# Schematic.net
KiCad netlist of a schematic drawn in EAGLE
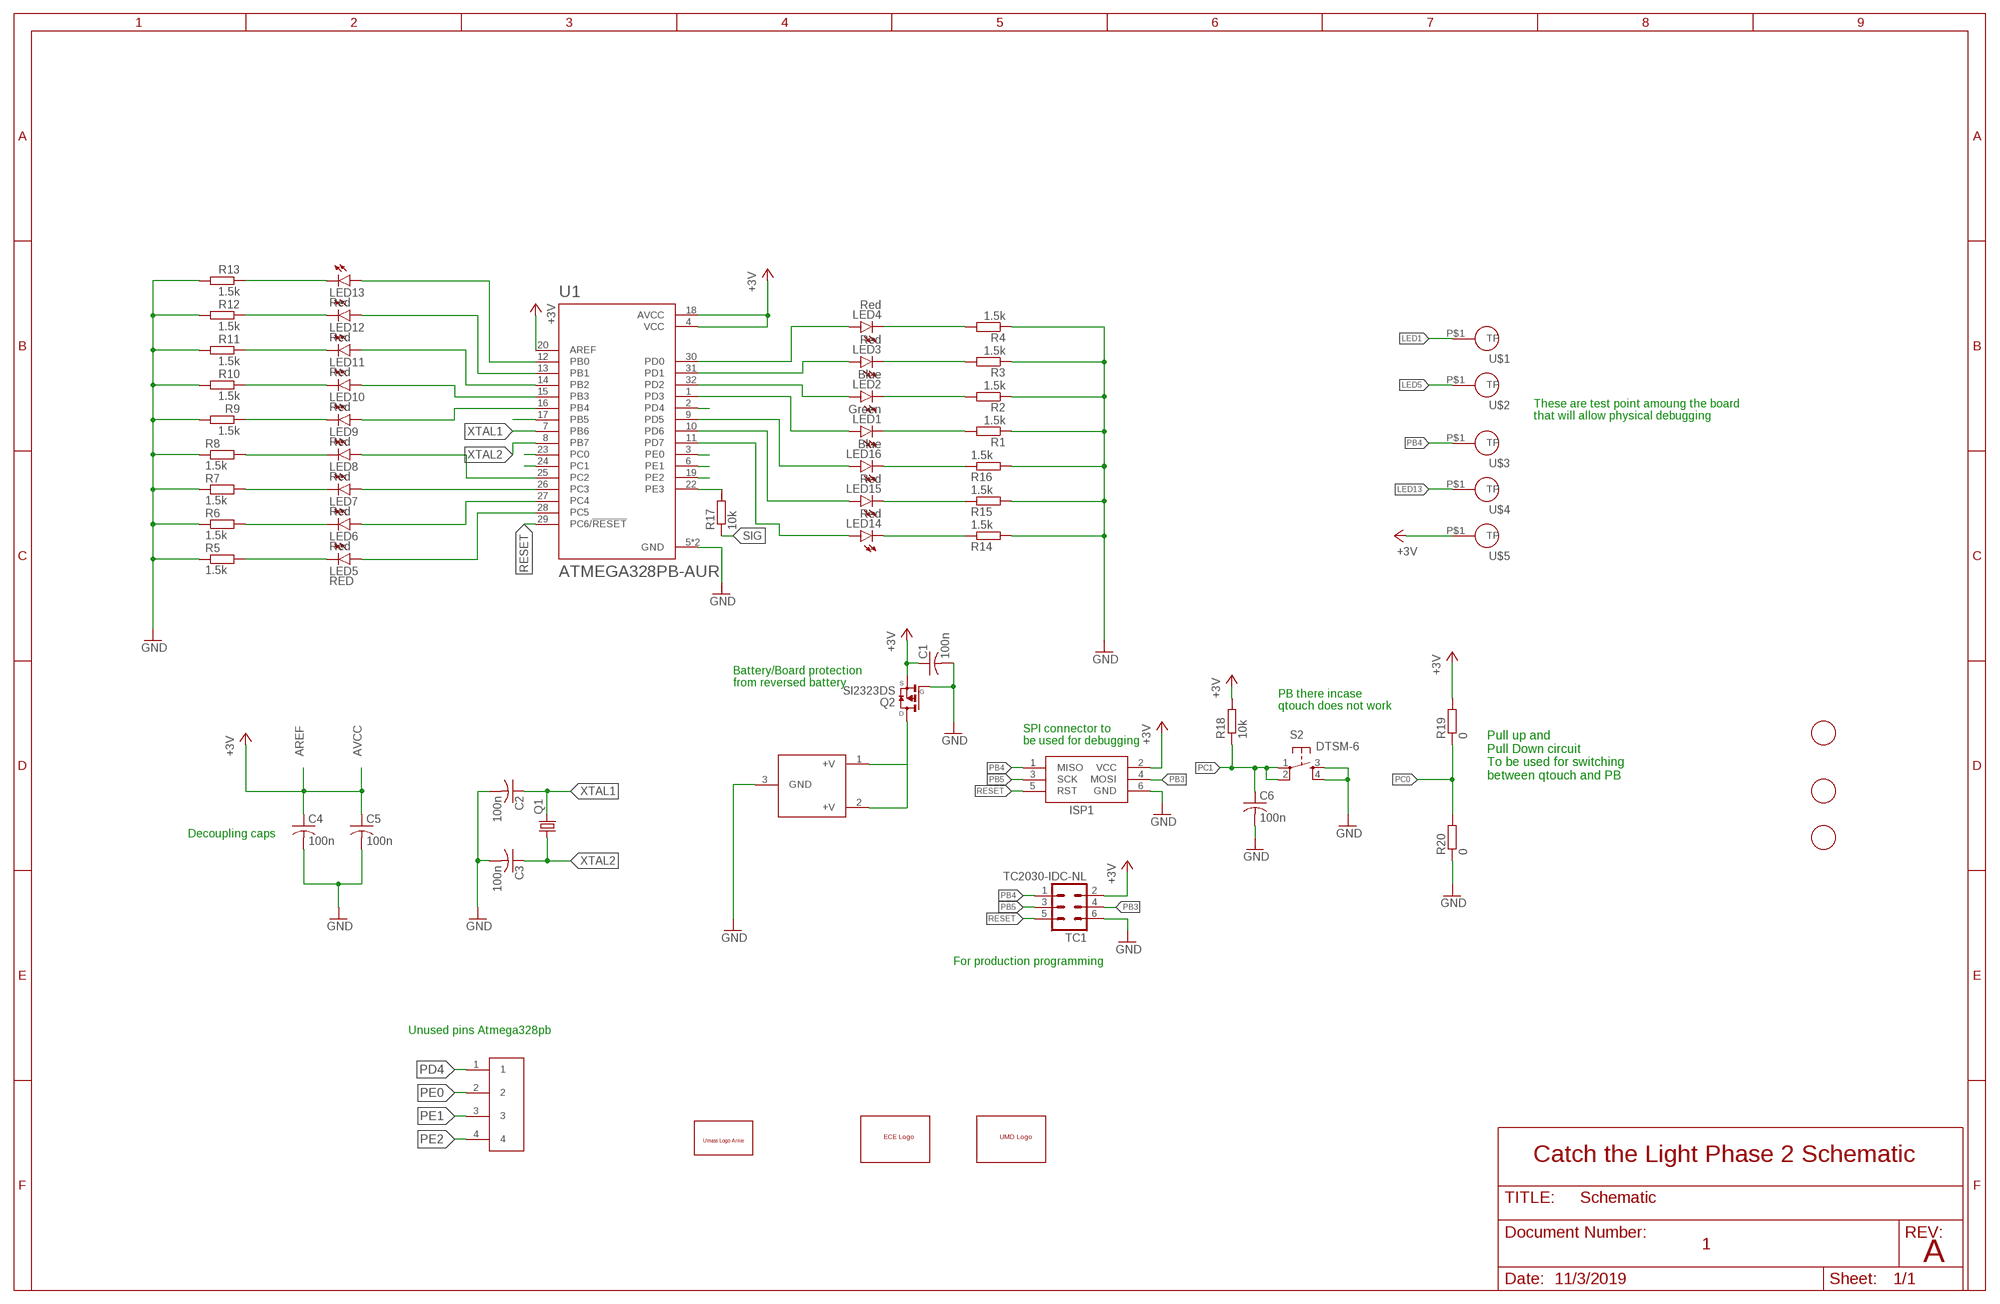
[diagram p0: schematic, sheet 1]

(export (version "E")
  (design (tool "Eeschema 10.0.6"))
  (components
    (comp (ref "C1")
      (value "100n")
      (footprint "eagle-import:C0805")
      (libsource (lib "eagle-import") (part "C-USC0805"))
    )
    (comp (ref "C2")
      (value "100n")
      (footprint "eagle-import:C0805")
      (libsource (lib "eagle-import") (part "C-USC0805"))
    )
    (comp (ref "C3")
      (value "100n")
      (footprint "eagle-import:C0805")
      (libsource (lib "eagle-import") (part "C-USC0805"))
    )
    (comp (ref "C4")
      (value "100n")
      (footprint "eagle-import:C0805")
      (libsource (lib "eagle-import") (part "C-USC0805"))
    )
    (comp (ref "C5")
      (value "100n")
      (footprint "eagle-import:C0805")
      (libsource (lib "eagle-import") (part "C-USC0805"))
    )
    (comp (ref "C6")
      (value "100n")
      (footprint "eagle-import:C0805")
      (libsource (lib "eagle-import") (part "C-USC0805"))
    )
    (comp (ref "CR2032")
      (value "BC-2003SMD")
      (footprint "eagle-import:BC-2003")
      (libsource (lib "eagle-import") (part "BC-2003SMD"))
    )
    (comp (ref "ISP1")
      (value "AVRISP-6")
      (footprint "eagle-import:AVRISP")
      (libsource (lib "eagle-import") (part "AVRISP-6"))
    )
    (comp (ref "LED1")
      (value "Green")
      (footprint "eagle-import:CHIP-LED0805")
      (libsource (lib "eagle-import") (part "LEDCHIP-LED0805"))
    )
    (comp (ref "LED2")
      (value "Blue")
      (footprint "eagle-import:CHIP-LED0805")
      (libsource (lib "eagle-import") (part "LEDCHIP-LED0805"))
    )
    (comp (ref "LED3")
      (value "Red")
      (footprint "eagle-import:CHIP-LED0805")
      (libsource (lib "eagle-import") (part "LEDCHIP-LED0805"))
    )
    (comp (ref "LED4")
      (value "Red")
      (footprint "eagle-import:CHIP-LED0805")
      (libsource (lib "eagle-import") (part "LEDCHIP-LED0805"))
    )
    (comp (ref "LED5")
      (value "RED")
      (footprint "eagle-import:CHIP-LED0805")
      (libsource (lib "eagle-import") (part "LEDCHIP-LED0805"))
    )
    (comp (ref "LED6")
      (value "Red")
      (footprint "eagle-import:CHIP-LED0805")
      (libsource (lib "eagle-import") (part "LEDCHIP-LED0805"))
    )
    (comp (ref "LED7")
      (value "Red")
      (footprint "eagle-import:CHIP-LED0805")
      (libsource (lib "eagle-import") (part "LEDCHIP-LED0805"))
    )
    (comp (ref "LED8")
      (value "Red")
      (footprint "eagle-import:CHIP-LED0805")
      (libsource (lib "eagle-import") (part "LEDCHIP-LED0805"))
    )
    (comp (ref "LED9")
      (value "Red")
      (footprint "eagle-import:CHIP-LED0805")
      (libsource (lib "eagle-import") (part "LEDCHIP-LED0805"))
    )
    (comp (ref "LED10")
      (value "Red")
      (footprint "eagle-import:CHIP-LED0805")
      (libsource (lib "eagle-import") (part "LEDCHIP-LED0805"))
    )
    (comp (ref "LED11")
      (value "Red")
      (footprint "eagle-import:CHIP-LED0805")
      (libsource (lib "eagle-import") (part "LEDCHIP-LED0805"))
    )
    (comp (ref "LED12")
      (value "Red")
      (footprint "eagle-import:CHIP-LED0805")
      (libsource (lib "eagle-import") (part "LEDCHIP-LED0805"))
    )
    (comp (ref "LED13")
      (value "Red")
      (footprint "eagle-import:CHIP-LED0805")
      (libsource (lib "eagle-import") (part "LEDCHIP-LED0805"))
    )
    (comp (ref "LED14")
      (value "Red")
      (footprint "eagle-import:CHIP-LED0805")
      (libsource (lib "eagle-import") (part "LEDCHIP-LED0805"))
    )
    (comp (ref "LED15")
      (value "Red")
      (footprint "eagle-import:CHIP-LED0805")
      (libsource (lib "eagle-import") (part "LEDCHIP-LED0805"))
    )
    (comp (ref "LED16")
      (value "Blue")
      (footprint "eagle-import:CHIP-LED0805")
      (libsource (lib "eagle-import") (part "LEDCHIP-LED0805"))
    )
    (comp (ref "Q1")
      (value "CRYSTALHC49UP")
      (footprint "eagle-import:HC49UP")
      (libsource (lib "eagle-import") (part "CRYSTALHC49UP"))
    )
    (comp (ref "Q2")
      (value "SI2323DS")
      (footprint "eagle-import:SOT23")
      (fields (field (name "MF") "Vishay Siliconix"))
      (libsource (lib "eagle-import") (part "SI2323DS"))
    )
    (comp (ref "R1")
      (value "1.5k")
      (footprint "eagle-import:R0805")
      (libsource (lib "eagle-import") (part "R-EU_R0805"))
    )
    (comp (ref "R2")
      (value "1.5k")
      (footprint "eagle-import:R0805")
      (libsource (lib "eagle-import") (part "R-EU_R0805"))
    )
    (comp (ref "R3")
      (value "1.5k")
      (footprint "eagle-import:R0805")
      (libsource (lib "eagle-import") (part "R-EU_R0805"))
    )
    (comp (ref "R4")
      (value "1.5k")
      (footprint "eagle-import:R0805")
      (libsource (lib "eagle-import") (part "R-EU_R0805"))
    )
    (comp (ref "R5")
      (value "1.5k")
      (footprint "eagle-import:R0805")
      (libsource (lib "eagle-import") (part "R-EU_R0805"))
    )
    (comp (ref "R6")
      (value "1.5k")
      (footprint "eagle-import:R0805")
      (libsource (lib "eagle-import") (part "R-EU_R0805"))
    )
    (comp (ref "R7")
      (value "1.5k")
      (footprint "eagle-import:R0805")
      (libsource (lib "eagle-import") (part "R-EU_R0805"))
    )
    (comp (ref "R8")
      (value "1.5k")
      (footprint "eagle-import:R0805")
      (libsource (lib "eagle-import") (part "R-EU_R0805"))
    )
    (comp (ref "R9")
      (value "1.5k")
      (footprint "eagle-import:R0805")
      (libsource (lib "eagle-import") (part "R-EU_R0805"))
    )
    (comp (ref "R10")
      (value "1.5k")
      (footprint "eagle-import:R0805")
      (libsource (lib "eagle-import") (part "R-EU_R0805"))
    )
    (comp (ref "R11")
      (value "1.5k")
      (footprint "eagle-import:R0805")
      (libsource (lib "eagle-import") (part "R-EU_R0805"))
    )
    (comp (ref "R12")
      (value "1.5k")
      (footprint "eagle-import:R0805")
      (libsource (lib "eagle-import") (part "R-EU_R0805"))
    )
    (comp (ref "R13")
      (value "1.5k")
      (footprint "eagle-import:R0805")
      (libsource (lib "eagle-import") (part "R-EU_R0805"))
    )
    (comp (ref "R14")
      (value "1.5k")
      (footprint "eagle-import:R0805")
      (libsource (lib "eagle-import") (part "R-EU_R0805"))
    )
    (comp (ref "R15")
      (value "1.5k")
      (footprint "eagle-import:R0805")
      (libsource (lib "eagle-import") (part "R-EU_R0805"))
    )
    (comp (ref "R16")
      (value "1.5k")
      (footprint "eagle-import:R0805")
      (libsource (lib "eagle-import") (part "R-EU_R0805"))
    )
    (comp (ref "R17")
      (value "10k")
      (footprint "eagle-import:R0805")
      (libsource (lib "eagle-import") (part "R-EU_R0805"))
    )
    (comp (ref "R18")
      (value "10k")
      (footprint "eagle-import:R0805")
      (libsource (lib "eagle-import") (part "R-EU_R0805"))
    )
    (comp (ref "R19")
      (value "0")
      (footprint "eagle-import:R0805")
      (libsource (lib "eagle-import") (part "R-EU_R0805"))
    )
    (comp (ref "R20")
      (value "0")
      (footprint "eagle-import:R0805")
      (libsource (lib "eagle-import") (part "R-EU_R0805"))
    )
    (comp (ref "S2")
      (value "DTSM-6")
      (footprint "eagle-import:DTSM-6")
      (libsource (lib "eagle-import") (part "DTSM-6"))
    )
    (comp (ref "TC1")
      (value "TC2030-IDC-NL")
      (footprint "eagle-import:TC2030-IDC-NL")
      (libsource (lib "eagle-import") (part "TC2030-IDC-NL"))
    )
    (comp (ref "U$1")
      (value "TEST_POINT")
      (footprint "eagle-import:TEST_POINT")
      (libsource (lib "eagle-import") (part "TEST_POINT"))
    )
    (comp (ref "U$2")
      (value "TEST_POINT")
      (footprint "eagle-import:TEST_POINT")
      (libsource (lib "eagle-import") (part "TEST_POINT"))
    )
    (comp (ref "U$3")
      (value "TEST_POINT")
      (footprint "eagle-import:TEST_POINT")
      (libsource (lib "eagle-import") (part "TEST_POINT"))
    )
    (comp (ref "U$4")
      (value "TEST_POINT")
      (footprint "eagle-import:TEST_POINT")
      (libsource (lib "eagle-import") (part "TEST_POINT"))
    )
    (comp (ref "U$5")
      (value "TEST_POINT")
      (footprint "eagle-import:TEST_POINT")
      (libsource (lib "eagle-import") (part "TEST_POINT"))
    )
    (comp (ref "U$6")
      (value "PINHEADER")
      (footprint "eagle-import:HEADERPIN")
      (libsource (lib "eagle-import") (part "PINHEADER"))
    )
    (comp (ref "U$7")
      (value "FIDUCIAL")
      (footprint "eagle-import:FIDUCIAL_1MM")
      (libsource (lib "eagle-import") (part "FIDUCIAL"))
    )
    (comp (ref "U$8")
      (value "FIDUCIAL")
      (footprint "eagle-import:FIDUCIAL_1MM")
      (libsource (lib "eagle-import") (part "FIDUCIAL"))
    )
    (comp (ref "U$9")
      (value "FIDUCIAL")
      (footprint "eagle-import:FIDUCIAL_1MM")
      (libsource (lib "eagle-import") (part "FIDUCIAL"))
    )
    (comp (ref "U$10")
      (value "UMASSLGOARNIE")
      (footprint "eagle-import:UMASSLOGOARNIE")
      (libsource (lib "eagle-import") (part "UMASSLGOARNIE"))
    )
    (comp (ref "U$11")
      (value "ECE_LOGO")
      (footprint "eagle-import:ECE")
      (libsource (lib "eagle-import") (part "ECE_LOGO"))
    )
    (comp (ref "U$12")
      (value "UMDLOGO")
      (footprint "eagle-import:UMDLOGO")
      (libsource (lib "eagle-import") (part "UMDLOGO"))
    )
    (comp (ref "U1")
      (value "ATMEGA328PB-AUR")
      (footprint "eagle-import:QFP80P900X900X120-32N")
      (fields (field (name "DIGI-KEY_PART_NUMBER") "ATMEGA328PB-AURCT-ND") (field (name "MF") "Microchip"))
      (libsource (lib "eagle-import") (part "ATMEGA328PB-AUR"))
    )
  )
  (nets
    (net (code "1") (name "+3V") (class "Default")
      (node (ref "C1") (pin "1") (pinfunction "1_1") (pintype "passive"))
      (node (ref "C4") (pin "1") (pinfunction "1_1") (pintype "passive"))
      (node (ref "C5") (pin "1") (pinfunction "1_1") (pintype "passive"))
      (node (ref "ISP1") (pin "2") (pinfunction "VCC_2") (pintype "power_in"))
      (node (ref "Q2") (pin "2") (pinfunction "S_2") (pintype "passive"))
      (node (ref "R18") (pin "2") (pinfunction "2_2") (pintype "passive"))
      (node (ref "R19") (pin "2") (pinfunction "2_2") (pintype "passive"))
      (node (ref "TC1") (pin "2") (pinfunction "2_2") (pintype "passive"))
      (node (ref "U$5") (pin "P$1") (pinfunction "TP_P$1") (pintype "bidirectional"))
      (node (ref "U1") (pin "18") (pinfunction "AVCC_18") (pintype "power_in"))
      (node (ref "U1") (pin "20") (pinfunction "AREF_20") (pintype "input"))
      (node (ref "U1") (pin "4") (pinfunction "VCC_4") (pintype "power_in"))
    )
    (net (code "2") (name "GND") (class "Default")
      (node (ref "C1") (pin "2") (pinfunction "2_2") (pintype "passive"))
      (node (ref "C2") (pin "2") (pinfunction "2_2") (pintype "passive"))
      (node (ref "C3") (pin "2") (pinfunction "2_2") (pintype "passive"))
      (node (ref "C4") (pin "2") (pinfunction "2_2") (pintype "passive"))
      (node (ref "C5") (pin "2") (pinfunction "2_2") (pintype "passive"))
      (node (ref "C6") (pin "2") (pinfunction "2_2") (pintype "passive"))
      (node (ref "CR2032") (pin "3") (pinfunction "GND_3") (pintype "bidirectional"))
      (node (ref "ISP1") (pin "6") (pinfunction "GND_6") (pintype "power_in"))
      (node (ref "Q2") (pin "1") (pinfunction "G_1") (pintype "passive"))
      (node (ref "R1") (pin "1") (pinfunction "1_1") (pintype "passive"))
      (node (ref "R10") (pin "2") (pinfunction "2_2") (pintype "passive"))
      (node (ref "R11") (pin "2") (pinfunction "2_2") (pintype "passive"))
      (node (ref "R12") (pin "2") (pinfunction "2_2") (pintype "passive"))
      (node (ref "R13") (pin "2") (pinfunction "2_2") (pintype "passive"))
      (node (ref "R14") (pin "2") (pinfunction "2_2") (pintype "passive"))
      (node (ref "R15") (pin "2") (pinfunction "2_2") (pintype "passive"))
      (node (ref "R16") (pin "2") (pinfunction "2_2") (pintype "passive"))
      (node (ref "R2") (pin "1") (pinfunction "1_1") (pintype "passive"))
      (node (ref "R20") (pin "1") (pinfunction "1_1") (pintype "passive"))
      (node (ref "R3") (pin "1") (pinfunction "1_1") (pintype "passive"))
      (node (ref "R4") (pin "1") (pinfunction "1_1") (pintype "passive"))
      (node (ref "R5") (pin "1") (pinfunction "1_1") (pintype "passive"))
      (node (ref "R6") (pin "1") (pinfunction "1_1") (pintype "passive"))
      (node (ref "R7") (pin "1") (pinfunction "1_1") (pintype "passive"))
      (node (ref "R8") (pin "1") (pinfunction "1_1") (pintype "passive"))
      (node (ref "R9") (pin "2") (pinfunction "2_2") (pintype "passive"))
      (node (ref "S2") (pin "3") (pinfunction "3_3") (pintype "passive"))
      (node (ref "S2") (pin "4") (pinfunction "4_4") (pintype "passive"))
      (node (ref "TC1") (pin "6") (pinfunction "6_6") (pintype "passive"))
      (node (ref "U1") (pin "21") (pinfunction "GND_21") (pintype "power_in"))
      (node (ref "U1") (pin "5") (pinfunction "GND_5") (pintype "power_in"))
    )
    (net (code "3") (name "LED1") (class "Default")
      (node (ref "LED1") (pin "A") (pinfunction "A_A") (pintype "passive"))
      (node (ref "U$1") (pin "P$1") (pinfunction "TP_P$1") (pintype "bidirectional"))
      (node (ref "U1") (pin "1") (pinfunction "PD3_1") (pintype "bidirectional"))
    )
    (net (code "4") (name "LED5") (class "Default")
      (node (ref "LED5") (pin "A") (pinfunction "A_A") (pintype "passive"))
      (node (ref "U$2") (pin "P$1") (pinfunction "TP_P$1") (pintype "bidirectional"))
      (node (ref "U1") (pin "28") (pinfunction "PC5_28") (pintype "bidirectional"))
    )
    (net (code "5") (name "LED13") (class "Default")
      (node (ref "LED13") (pin "A") (pinfunction "A_A") (pintype "passive"))
      (node (ref "U$4") (pin "P$1") (pinfunction "TP_P$1") (pintype "bidirectional"))
      (node (ref "U1") (pin "12") (pinfunction "PB0_12") (pintype "bidirectional"))
    )
    (net (code "6") (name "Net-(LED1-PadC)") (class "Default")
      (node (ref "LED1") (pin "C") (pinfunction "C_C") (pintype "passive"))
      (node (ref "R1") (pin "2") (pinfunction "2_2") (pintype "passive"))
    )
    (net (code "7") (name "Net-(LED2-PadC)") (class "Default")
      (node (ref "LED2") (pin "C") (pinfunction "C_C") (pintype "passive"))
      (node (ref "R2") (pin "2") (pinfunction "2_2") (pintype "passive"))
    )
    (net (code "8") (name "Net-(LED3-PadC)") (class "Default")
      (node (ref "LED3") (pin "C") (pinfunction "C_C") (pintype "passive"))
      (node (ref "R3") (pin "2") (pinfunction "2_2") (pintype "passive"))
    )
    (net (code "9") (name "Net-(LED4-PadC)") (class "Default")
      (node (ref "LED4") (pin "C") (pinfunction "C_C") (pintype "passive"))
      (node (ref "R4") (pin "2") (pinfunction "2_2") (pintype "passive"))
    )
    (net (code "10") (name "Net-(LED5-PadC)") (class "Default")
      (node (ref "LED5") (pin "C") (pinfunction "C_C") (pintype "passive"))
      (node (ref "R5") (pin "2") (pinfunction "2_2") (pintype "passive"))
    )
    (net (code "11") (name "Net-(LED6-PadC)") (class "Default")
      (node (ref "LED6") (pin "C") (pinfunction "C_C") (pintype "passive"))
      (node (ref "R6") (pin "2") (pinfunction "2_2") (pintype "passive"))
    )
    (net (code "12") (name "Net-(LED7-PadC)") (class "Default")
      (node (ref "LED7") (pin "C") (pinfunction "C_C") (pintype "passive"))
      (node (ref "R7") (pin "2") (pinfunction "2_2") (pintype "passive"))
    )
    (net (code "13") (name "Net-(LED8-PadC)") (class "Default")
      (node (ref "LED8") (pin "C") (pinfunction "C_C") (pintype "passive"))
      (node (ref "R8") (pin "2") (pinfunction "2_2") (pintype "passive"))
    )
    (net (code "14") (name "Net-(LED9-PadC)") (class "Default")
      (node (ref "LED9") (pin "C") (pinfunction "C_C") (pintype "passive"))
      (node (ref "R9") (pin "1") (pinfunction "1_1") (pintype "passive"))
    )
    (net (code "15") (name "Net-(LED10-PadC)") (class "Default")
      (node (ref "LED10") (pin "C") (pinfunction "C_C") (pintype "passive"))
      (node (ref "R10") (pin "1") (pinfunction "1_1") (pintype "passive"))
    )
    (net (code "16") (name "Net-(LED11-PadC)") (class "Default")
      (node (ref "LED11") (pin "C") (pinfunction "C_C") (pintype "passive"))
      (node (ref "R11") (pin "1") (pinfunction "1_1") (pintype "passive"))
    )
    (net (code "17") (name "Net-(LED12-PadC)") (class "Default")
      (node (ref "LED12") (pin "C") (pinfunction "C_C") (pintype "passive"))
      (node (ref "R12") (pin "1") (pinfunction "1_1") (pintype "passive"))
    )
    (net (code "18") (name "Net-(LED13-PadC)") (class "Default")
      (node (ref "LED13") (pin "C") (pinfunction "C_C") (pintype "passive"))
      (node (ref "R13") (pin "1") (pinfunction "1_1") (pintype "passive"))
    )
    (net (code "19") (name "Net-(LED14-PadC)") (class "Default")
      (node (ref "LED14") (pin "C") (pinfunction "C_C") (pintype "passive"))
      (node (ref "R14") (pin "1") (pinfunction "1_1") (pintype "passive"))
    )
    (net (code "20") (name "Net-(LED15-PadC)") (class "Default")
      (node (ref "LED15") (pin "C") (pinfunction "C_C") (pintype "passive"))
      (node (ref "R15") (pin "1") (pinfunction "1_1") (pintype "passive"))
    )
    (net (code "21") (name "Net-(LED16-PadC)") (class "Default")
      (node (ref "LED16") (pin "C") (pinfunction "C_C") (pintype "passive"))
      (node (ref "R16") (pin "1") (pinfunction "1_1") (pintype "passive"))
    )
    (net (code "22") (name "Net-(Q2-D)") (class "Default")
      (node (ref "CR2032") (pin "1") (pinfunction "+V_1") (pintype "bidirectional"))
      (node (ref "CR2032") (pin "2") (pinfunction "+V_2") (pintype "bidirectional"))
      (node (ref "Q2") (pin "3") (pinfunction "D_3") (pintype "passive"))
    )
    (net (code "23") (name "Net-(U1-PB1)") (class "Default")
      (node (ref "LED12") (pin "A") (pinfunction "A_A") (pintype "passive"))
      (node (ref "U1") (pin "13") (pinfunction "PB1_13") (pintype "bidirectional"))
    )
    (net (code "24") (name "Net-(U1-PB2)") (class "Default")
      (node (ref "LED11") (pin "A") (pinfunction "A_A") (pintype "passive"))
      (node (ref "U1") (pin "14") (pinfunction "PB2_14") (pintype "bidirectional"))
    )
    (net (code "25") (name "Net-(U1-PC2)") (class "Default")
      (node (ref "LED8") (pin "A") (pinfunction "A_A") (pintype "passive"))
      (node (ref "U1") (pin "25") (pinfunction "PC2_25") (pintype "bidirectional"))
    )
    (net (code "26") (name "Net-(U1-PC3)") (class "Default")
      (node (ref "LED7") (pin "A") (pinfunction "A_A") (pintype "passive"))
      (node (ref "U1") (pin "26") (pinfunction "PC3_26") (pintype "bidirectional"))
    )
    (net (code "27") (name "Net-(U1-PC4)") (class "Default")
      (node (ref "LED6") (pin "A") (pinfunction "A_A") (pintype "passive"))
      (node (ref "U1") (pin "27") (pinfunction "PC4_27") (pintype "bidirectional"))
    )
    (net (code "28") (name "Net-(U1-PD0)") (class "Default")
      (node (ref "LED4") (pin "A") (pinfunction "A_A") (pintype "passive"))
      (node (ref "U1") (pin "30") (pinfunction "PD0_30") (pintype "bidirectional"))
    )
    (net (code "29") (name "Net-(U1-PD1)") (class "Default")
      (node (ref "LED3") (pin "A") (pinfunction "A_A") (pintype "passive"))
      (node (ref "U1") (pin "31") (pinfunction "PD1_31") (pintype "bidirectional"))
    )
    (net (code "30") (name "Net-(U1-PD2)") (class "Default")
      (node (ref "LED2") (pin "A") (pinfunction "A_A") (pintype "passive"))
      (node (ref "U1") (pin "32") (pinfunction "PD2_32") (pintype "bidirectional"))
    )
    (net (code "31") (name "Net-(U1-PD5)") (class "Default")
      (node (ref "LED16") (pin "A") (pinfunction "A_A") (pintype "passive"))
      (node (ref "U1") (pin "9") (pinfunction "PD5_9") (pintype "bidirectional"))
    )
    (net (code "32") (name "Net-(U1-PD6)") (class "Default")
      (node (ref "LED15") (pin "A") (pinfunction "A_A") (pintype "passive"))
      (node (ref "U1") (pin "10") (pinfunction "PD6_10") (pintype "bidirectional"))
    )
    (net (code "33") (name "Net-(U1-PD7)") (class "Default")
      (node (ref "LED14") (pin "A") (pinfunction "A_A") (pintype "passive"))
      (node (ref "U1") (pin "11") (pinfunction "PD7_11") (pintype "bidirectional"))
    )
    (net (code "34") (name "Net-(U1-PE3)") (class "Default")
      (node (ref "R17") (pin "2") (pinfunction "2_2") (pintype "passive"))
      (node (ref "U1") (pin "22") (pinfunction "PE3_22") (pintype "bidirectional"))
    )
    (net (code "35") (name "PB3") (class "Default")
      (node (ref "ISP1") (pin "4") (pinfunction "MOSI_4") (pintype "output"))
      (node (ref "LED10") (pin "A") (pinfunction "A_A") (pintype "passive"))
      (node (ref "TC1") (pin "4") (pinfunction "4_4") (pintype "passive"))
      (node (ref "U1") (pin "15") (pinfunction "PB3_15") (pintype "bidirectional"))
    )
    (net (code "36") (name "PB4") (class "Default")
      (node (ref "ISP1") (pin "1") (pinfunction "MISO_1") (pintype "input"))
      (node (ref "LED9") (pin "A") (pinfunction "A_A") (pintype "passive"))
      (node (ref "TC1") (pin "1") (pinfunction "1_1") (pintype "passive"))
      (node (ref "U$3") (pin "P$1") (pinfunction "TP_P$1") (pintype "bidirectional"))
      (node (ref "U1") (pin "16") (pinfunction "PB4_16") (pintype "bidirectional"))
    )
    (net (code "37") (name "PB5") (class "Default")
      (node (ref "ISP1") (pin "3") (pinfunction "SCK_3") (pintype "output"))
      (node (ref "TC1") (pin "3") (pinfunction "3_3") (pintype "passive"))
      (node (ref "U1") (pin "17") (pinfunction "PB5_17") (pintype "bidirectional"))
    )
    (net (code "38") (name "PC0") (class "Default")
      (node (ref "R19") (pin "1") (pinfunction "1_1") (pintype "passive"))
      (node (ref "R20") (pin "2") (pinfunction "2_2") (pintype "passive"))
      (node (ref "U1") (pin "23") (pinfunction "PC0_23") (pintype "bidirectional"))
    )
    (net (code "39") (name "PC1") (class "Default")
      (node (ref "C6") (pin "1") (pinfunction "1_1") (pintype "passive"))
      (node (ref "R18") (pin "1") (pinfunction "1_1") (pintype "passive"))
      (node (ref "S2") (pin "1") (pinfunction "1_1") (pintype "passive"))
      (node (ref "S2") (pin "2") (pinfunction "2_2") (pintype "passive"))
      (node (ref "U1") (pin "24") (pinfunction "PC1_24") (pintype "bidirectional"))
    )
    (net (code "40") (name "PD4") (class "Default")
      (node (ref "U$6") (pin "1") (pinfunction "1_1") (pintype "bidirectional"))
      (node (ref "U1") (pin "2") (pinfunction "PD4_2") (pintype "bidirectional"))
    )
    (net (code "41") (name "PE0") (class "Default")
      (node (ref "U$6") (pin "2") (pinfunction "2_2") (pintype "bidirectional"))
      (node (ref "U1") (pin "3") (pinfunction "PE0_3") (pintype "bidirectional"))
    )
    (net (code "42") (name "PE1") (class "Default")
      (node (ref "U$6") (pin "3") (pinfunction "3_3") (pintype "bidirectional"))
      (node (ref "U1") (pin "6") (pinfunction "PE1_6") (pintype "bidirectional"))
    )
    (net (code "43") (name "PE2") (class "Default")
      (node (ref "U$6") (pin "4") (pinfunction "4_4") (pintype "bidirectional"))
      (node (ref "U1") (pin "19") (pinfunction "PE2_19") (pintype "bidirectional"))
    )
    (net (code "44") (name "RESET") (class "Default")
      (node (ref "ISP1") (pin "5") (pinfunction "RST_5") (pintype "output"))
      (node (ref "TC1") (pin "5") (pinfunction "5_5") (pintype "passive"))
      (node (ref "U1") (pin "29") (pinfunction "PC6/~{RESET}_29") (pintype "bidirectional"))
    )
    (net (code "45") (name "SIG") (class "Default")
      (node (ref "R17") (pin "1") (pinfunction "1_1") (pintype "passive"))
    )
    (net (code "46") (name "XTAL1") (class "Default")
      (node (ref "C2") (pin "1") (pinfunction "1_1") (pintype "passive"))
      (node (ref "Q1") (pin "2") (pinfunction "2_2") (pintype "passive"))
      (node (ref "U1") (pin "7") (pinfunction "PB6_7") (pintype "bidirectional"))
    )
    (net (code "47") (name "XTAL2") (class "Default")
      (node (ref "C3") (pin "1") (pinfunction "1_1") (pintype "passive"))
      (node (ref "Q1") (pin "1") (pinfunction "1_1") (pintype "passive"))
      (node (ref "U1") (pin "8") (pinfunction "PB7_8") (pintype "bidirectional"))
    )
  )
)
